# A328.net
KiCad netlist of a schematic drawn in EAGLE
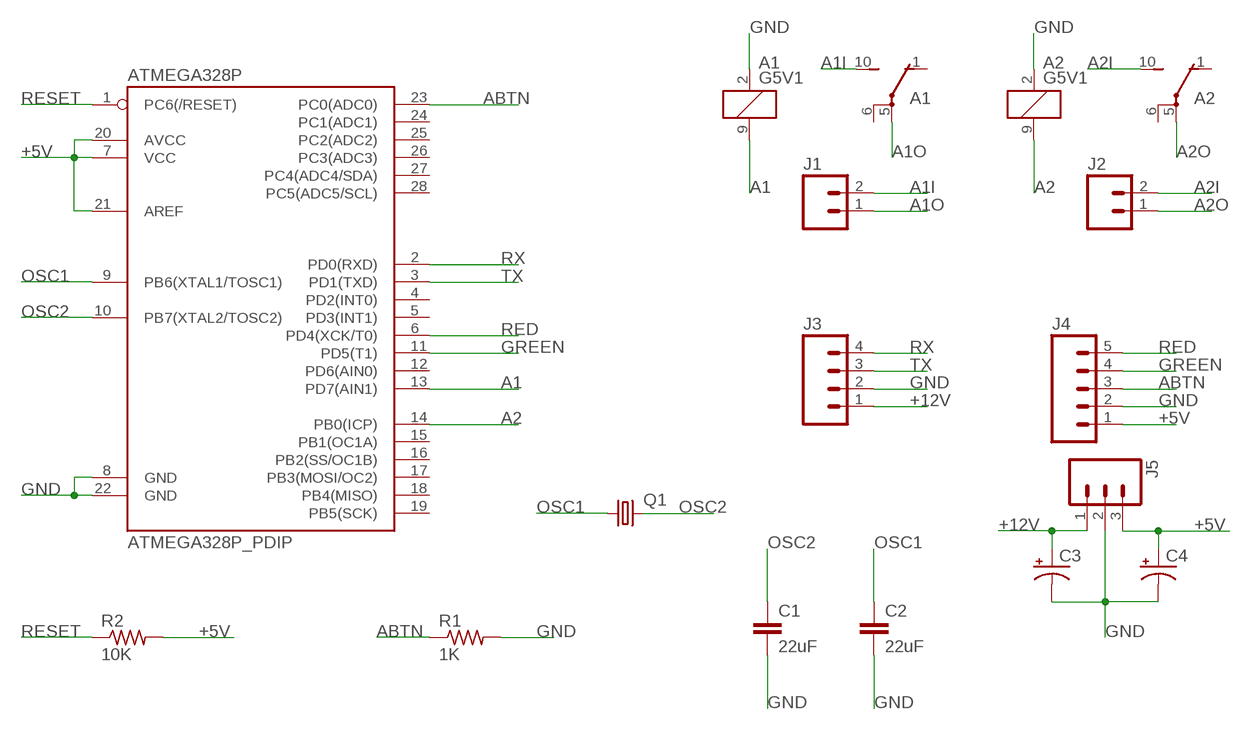
[diagram p0: schematic, sheet 1]

(export (version "E")
  (design (tool "Eeschema 10.0.6"))
  (components
    (comp (ref "A1")
      (value "G5V1")
      (footprint "eagle-import:G5V1")
      (fields (field (name "MPN") "G5V-1-DC24"))
      (libsource (lib "eagle-import") (part "G5V1"))
    )
    (comp (ref "A2")
      (value "G5V1")
      (footprint "eagle-import:G5V1")
      (fields (field (name "MPN") "G5V-1-DC24"))
      (libsource (lib "eagle-import") (part "G5V1"))
    )
    (comp (ref "ATMEGA328P")
      (value "ATMEGA328P_PDIP")
      (footprint "eagle-import:DIL28-3")
      (libsource (lib "eagle-import") (part "ATMEGA328P_PDIP"))
    )
    (comp (ref "C1")
      (value "22uF")
      (footprint "eagle-import:CAP-PTH-SMALL-KIT")
      (libsource (lib "eagle-import") (part "CAPKIT"))
    )
    (comp (ref "C2")
      (value "22uF")
      (footprint "eagle-import:CAP-PTH-SMALL-KIT")
      (libsource (lib "eagle-import") (part "CAPKIT"))
    )
    (comp (ref "C3")
      (value "10UF-25V-20%(PTH)")
      (footprint "eagle-import:CPOL-RADIAL-10UF-25V")
      (libsource (lib "eagle-import") (part "10UF-25V-20%(PTH)"))
    )
    (comp (ref "C4")
      (value "10UF-25V-20%(PTH)")
      (footprint "eagle-import:CPOL-RADIAL-10UF-25V")
      (libsource (lib "eagle-import") (part "10UF-25V-20%(PTH)"))
    )
    (comp (ref "J1")
      (value "M02PTH3")
      (footprint "eagle-import:1X02_LONGPADS")
      (libsource (lib "eagle-import") (part "M02PTH3"))
    )
    (comp (ref "J2")
      (value "M02PTH3")
      (footprint "eagle-import:1X02_LONGPADS")
      (libsource (lib "eagle-import") (part "M02PTH3"))
    )
    (comp (ref "J3")
      (value "M04NO_SILK_ALL_ROUND")
      (footprint "eagle-import:1X04_NO_SILK_ALL_ROUND")
      (libsource (lib "eagle-import") (part "M04NO_SILK_ALL_ROUND"))
    )
    (comp (ref "J4")
      (value "M05NO_SILK")
      (footprint "eagle-import:1X05_NO_SILK")
      (libsource (lib "eagle-import") (part "M05NO_SILK"))
    )
    (comp (ref "J5")
      (value "M03LONGPADS")
      (footprint "eagle-import:1X03_LONGPADS")
      (libsource (lib "eagle-import") (part "M03LONGPADS"))
    )
    (comp (ref "Q1")
      (value "CRYSTALHC49S")
      (footprint "eagle-import:HC49_S")
      (libsource (lib "eagle-import") (part "CRYSTALHC49S"))
    )
    (comp (ref "R1")
      (value "1K")
      (footprint "eagle-import:0204_7")
      (libsource (lib "eagle-import") (part "R-US_0204/7"))
    )
    (comp (ref "R2")
      (value "10K")
      (footprint "eagle-import:0204_7")
      (libsource (lib "eagle-import") (part "R-US_0204/7"))
    )
  )
  (nets
    (net (code "1") (name "/+5V") (class "Default")
      (node (ref "ATMEGA328P") (pin "20") (pinfunction "AVCC_20") (pintype "bidirectional"))
      (node (ref "ATMEGA328P") (pin "21") (pinfunction "AREF_21") (pintype "bidirectional"))
      (node (ref "ATMEGA328P") (pin "7") (pinfunction "VCC_7") (pintype "bidirectional"))
      (node (ref "C4") (pin "1") (pinfunction "+_1") (pintype "passive"))
      (node (ref "J4") (pin "1") (pinfunction "1_1") (pintype "passive"))
      (node (ref "J5") (pin "3") (pinfunction "3_3") (pintype "passive"))
      (node (ref "R2") (pin "2") (pinfunction "2_2") (pintype "passive"))
    )
    (net (code "2") (name "/+12V") (class "Default")
      (node (ref "C3") (pin "1") (pinfunction "+_1") (pintype "passive"))
      (node (ref "J3") (pin "1") (pinfunction "1_1") (pintype "passive"))
      (node (ref "J5") (pin "1") (pinfunction "1_1") (pintype "passive"))
    )
    (net (code "3") (name "/A1") (class "Default")
      (node (ref "A1") (pin "9") (pinfunction "2_9") (pintype "passive"))
      (node (ref "ATMEGA328P") (pin "13") (pinfunction "PD7(AIN1)_13") (pintype "bidirectional"))
    )
    (net (code "4") (name "/A1I") (class "Default")
      (node (ref "A1") (pin "10") (pinfunction "S_10") (pintype "passive"))
      (node (ref "J1") (pin "2") (pinfunction "2_2") (pintype "passive"))
    )
    (net (code "5") (name "/A1O") (class "Default")
      (node (ref "A1") (pin "5") (pinfunction "P_5") (pintype "passive"))
      (node (ref "J1") (pin "1") (pinfunction "1_1") (pintype "passive"))
    )
    (net (code "6") (name "/A2") (class "Default")
      (node (ref "A2") (pin "9") (pinfunction "2_9") (pintype "passive"))
      (node (ref "ATMEGA328P") (pin "14") (pinfunction "PB0(ICP)_14") (pintype "bidirectional"))
    )
    (net (code "7") (name "/A2I") (class "Default")
      (node (ref "A2") (pin "10") (pinfunction "S_10") (pintype "passive"))
      (node (ref "J2") (pin "2") (pinfunction "2_2") (pintype "passive"))
    )
    (net (code "8") (name "/A2O") (class "Default")
      (node (ref "A2") (pin "5") (pinfunction "P_5") (pintype "passive"))
      (node (ref "J2") (pin "1") (pinfunction "1_1") (pintype "passive"))
    )
    (net (code "9") (name "/ABTN") (class "Default")
      (node (ref "ATMEGA328P") (pin "23") (pinfunction "PC0(ADC0)_23") (pintype "bidirectional"))
      (node (ref "J4") (pin "3") (pinfunction "3_3") (pintype "passive"))
      (node (ref "R1") (pin "1") (pinfunction "1_1") (pintype "passive"))
    )
    (net (code "10") (name "/GND") (class "Default")
      (node (ref "A1") (pin "2") (pinfunction "1_2") (pintype "passive"))
      (node (ref "A2") (pin "2") (pinfunction "1_2") (pintype "passive"))
      (node (ref "ATMEGA328P") (pin "22") (pinfunction "GND_22") (pintype "bidirectional"))
      (node (ref "ATMEGA328P") (pin "8") (pinfunction "GND_8") (pintype "bidirectional"))
      (node (ref "C1") (pin "2") (pinfunction "2_2") (pintype "passive"))
      (node (ref "C2") (pin "2") (pinfunction "2_2") (pintype "passive"))
      (node (ref "C3") (pin "2") (pinfunction "-_2") (pintype "passive"))
      (node (ref "C4") (pin "2") (pinfunction "-_2") (pintype "passive"))
      (node (ref "J3") (pin "2") (pinfunction "2_2") (pintype "passive"))
      (node (ref "J4") (pin "2") (pinfunction "2_2") (pintype "passive"))
      (node (ref "J5") (pin "2") (pinfunction "2_2") (pintype "passive"))
      (node (ref "R1") (pin "2") (pinfunction "2_2") (pintype "passive"))
    )
    (net (code "11") (name "/GREEN") (class "Default")
      (node (ref "ATMEGA328P") (pin "11") (pinfunction "PD5(T1)_11") (pintype "bidirectional"))
      (node (ref "J4") (pin "4") (pinfunction "4_4") (pintype "passive"))
    )
    (net (code "12") (name "/OSC1") (class "Default")
      (node (ref "ATMEGA328P") (pin "9") (pinfunction "PB6(XTAL1/TOSC1)_9") (pintype "bidirectional"))
      (node (ref "C2") (pin "1") (pinfunction "1_1") (pintype "passive"))
      (node (ref "Q1") (pin "1") (pinfunction "1_1") (pintype "passive"))
    )
    (net (code "13") (name "/OSC2") (class "Default")
      (node (ref "ATMEGA328P") (pin "10") (pinfunction "PB7(XTAL2/TOSC2)_10") (pintype "bidirectional"))
      (node (ref "C1") (pin "1") (pinfunction "1_1") (pintype "passive"))
      (node (ref "Q1") (pin "2") (pinfunction "2_2") (pintype "passive"))
    )
    (net (code "14") (name "/RED") (class "Default")
      (node (ref "ATMEGA328P") (pin "6") (pinfunction "PD4(XCK/T0)_6") (pintype "bidirectional"))
      (node (ref "J4") (pin "5") (pinfunction "5_5") (pintype "passive"))
    )
    (net (code "15") (name "/RESET") (class "Default")
      (node (ref "ATMEGA328P") (pin "1") (pinfunction "PC6(/RESET)_1") (pintype "bidirectional"))
      (node (ref "R2") (pin "1") (pinfunction "1_1") (pintype "passive"))
    )
    (net (code "16") (name "/RX") (class "Default")
      (node (ref "ATMEGA328P") (pin "2") (pinfunction "PD0(RXD)_2") (pintype "bidirectional"))
      (node (ref "J3") (pin "4") (pinfunction "4_4") (pintype "passive"))
    )
    (net (code "17") (name "/TX") (class "Default")
      (node (ref "ATMEGA328P") (pin "3") (pinfunction "PD1(TXD)_3") (pintype "bidirectional"))
      (node (ref "J3") (pin "3") (pinfunction "3_3") (pintype "passive"))
    )
    (net (code "18") (name "unconnected-(A1B-O-Pad1)") (class "Default")
      (node (ref "A1") (pin "1") (pinfunction "O_1") (pintype "passive"))
    )
    (net (code "19") (name "unconnected-(A1B-P-Pad6)") (class "Default")
      (node (ref "A1") (pin "6") (pinfunction "P_6") (pintype "passive"))
    )
    (net (code "20") (name "unconnected-(A2B-O-Pad1)") (class "Default")
      (node (ref "A2") (pin "1") (pinfunction "O_1") (pintype "passive"))
    )
    (net (code "21") (name "unconnected-(A2B-P-Pad6)") (class "Default")
      (node (ref "A2") (pin "6") (pinfunction "P_6") (pintype "passive"))
    )
    (net (code "22") (name "unconnected-(ATMEGA328P-PB1(OC1A)-Pad15)") (class "Default")
      (node (ref "ATMEGA328P") (pin "15") (pinfunction "PB1(OC1A)_15") (pintype "bidirectional"))
    )
    (net (code "23") (name "unconnected-(ATMEGA328P-PB2(SS{slash}OC1B)-Pad16)") (class "Default")
      (node (ref "ATMEGA328P") (pin "16") (pinfunction "PB2(SS/OC1B)_16") (pintype "bidirectional"))
    )
    (net (code "24") (name "unconnected-(ATMEGA328P-PB3(MOSI{slash}OC2)-Pad17)") (class "Default")
      (node (ref "ATMEGA328P") (pin "17") (pinfunction "PB3(MOSI/OC2)_17") (pintype "bidirectional"))
    )
    (net (code "25") (name "unconnected-(ATMEGA328P-PB4(MISO)-Pad18)") (class "Default")
      (node (ref "ATMEGA328P") (pin "18") (pinfunction "PB4(MISO)_18") (pintype "bidirectional"))
    )
    (net (code "26") (name "unconnected-(ATMEGA328P-PB5(SCK)-Pad19)") (class "Default")
      (node (ref "ATMEGA328P") (pin "19") (pinfunction "PB5(SCK)_19") (pintype "bidirectional"))
    )
    (net (code "27") (name "unconnected-(ATMEGA328P-PC1(ADC1)-Pad24)") (class "Default")
      (node (ref "ATMEGA328P") (pin "24") (pinfunction "PC1(ADC1)_24") (pintype "bidirectional"))
    )
    (net (code "28") (name "unconnected-(ATMEGA328P-PC2(ADC2)-Pad25)") (class "Default")
      (node (ref "ATMEGA328P") (pin "25") (pinfunction "PC2(ADC2)_25") (pintype "bidirectional"))
    )
    (net (code "29") (name "unconnected-(ATMEGA328P-PC3(ADC3)-Pad26)") (class "Default")
      (node (ref "ATMEGA328P") (pin "26") (pinfunction "PC3(ADC3)_26") (pintype "bidirectional"))
    )
    (net (code "30") (name "unconnected-(ATMEGA328P-PC4(ADC4{slash}SDA)-Pad27)") (class "Default")
      (node (ref "ATMEGA328P") (pin "27") (pinfunction "PC4(ADC4/SDA)_27") (pintype "bidirectional"))
    )
    (net (code "31") (name "unconnected-(ATMEGA328P-PC5(ADC5{slash}SCL)-Pad28)") (class "Default")
      (node (ref "ATMEGA328P") (pin "28") (pinfunction "PC5(ADC5/SCL)_28") (pintype "bidirectional"))
    )
    (net (code "32") (name "unconnected-(ATMEGA328P-PD2(INT0)-Pad4)") (class "Default")
      (node (ref "ATMEGA328P") (pin "4") (pinfunction "PD2(INT0)_4") (pintype "bidirectional"))
    )
    (net (code "33") (name "unconnected-(ATMEGA328P-PD3(INT1)-Pad5)") (class "Default")
      (node (ref "ATMEGA328P") (pin "5") (pinfunction "PD3(INT1)_5") (pintype "bidirectional"))
    )
    (net (code "34") (name "unconnected-(ATMEGA328P-PD6(AIN0)-Pad12)") (class "Default")
      (node (ref "ATMEGA328P") (pin "12") (pinfunction "PD6(AIN0)_12") (pintype "bidirectional"))
    )
  )
)
